# Keyboard.net
KiCad netlist of a schematic drawn in Altium Designer
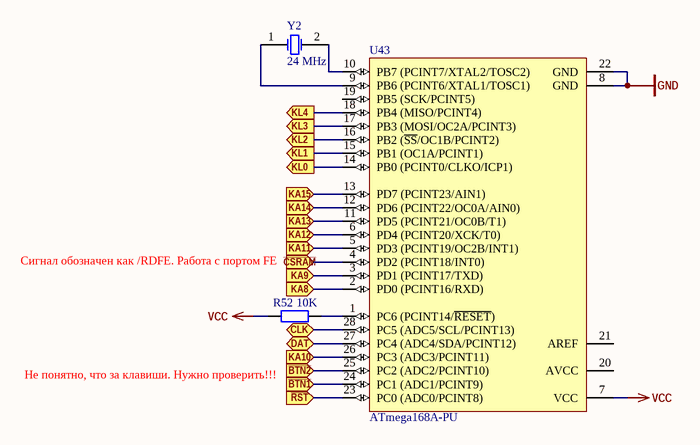
[diagram p0: Keyboard.SchDoc]

(export (version "E")
  (design (tool "Eeschema 10.0.6"))
  (components
    (comp (ref "R52")
      (value "10K")
      (footprint "Lenin:AXIAL-0.4")
      (description "Resistor")
      (fields (field (name "Comment") "Res2") (field (name "PUBLISHER") "Altium Limited"))
      (libsource (lib "Lenin") (part "Res2"))
    )
    (comp (ref "U43")
      (value "ATmega168A-PU")
      (footprint "28P3")
      (fields (field (name "PUBLISHER") "Altium Limited"))
      (libsource (lib "Atmel Microcontroller 8-Bit megaAVR") (part "ATmega168A-PU"))
    )
    (comp (ref "Y2")
      (value "24 MHz")
      (footprint "Lenin:HC25U")
      (description "Crystal Oscillator")
      (fields (field (name "PUBLISHER") "Altium Limited"))
      (libsource (lib "Lenin") (part "XTAL"))
    )
  )
  (nets
    (net (code "1") (name "/CLK") (class "Default")
      (node (ref "U43") (pin "28") (pinfunction "PC5_(ADC5/SCL/PCINT13)_28") (pintype "bidirectional"))
    )
    (net (code "2") (name "/DAT") (class "Default")
      (node (ref "U43") (pin "27") (pinfunction "PC4_(ADC4/SDA/PCINT12)_27") (pintype "bidirectional"))
    )
    (net (code "3") (name "/KA8") (class "Default")
      (node (ref "U43") (pin "2") (pinfunction "PD0_(PCINT16/RXD)_2") (pintype "bidirectional"))
    )
    (net (code "4") (name "/KA9") (class "Default")
      (node (ref "U43") (pin "3") (pinfunction "PD1_(PCINT17/TXD)_3") (pintype "bidirectional"))
    )
    (net (code "5") (name "/KA10") (class "Default")
      (node (ref "U43") (pin "26") (pinfunction "PC3_(ADC3/PCINT11)_26") (pintype "bidirectional"))
    )
    (net (code "6") (name "/KA11") (class "Default")
      (node (ref "U43") (pin "5") (pinfunction "PD3_(PCINT19/OC2B/INT1)_5") (pintype "bidirectional"))
    )
    (net (code "7") (name "/KA12") (class "Default")
      (node (ref "U43") (pin "6") (pinfunction "PD4_(PCINT20/XCK/T0)_6") (pintype "bidirectional"))
    )
    (net (code "8") (name "/KA13") (class "Default")
      (node (ref "U43") (pin "11") (pinfunction "PD5_(PCINT21/OC0B/T1)_11") (pintype "bidirectional"))
    )
    (net (code "9") (name "/KA14") (class "Default")
      (node (ref "U43") (pin "12") (pinfunction "PD6_(PCINT22/OC0A/AIN0)_12") (pintype "bidirectional"))
    )
    (net (code "10") (name "/KA15") (class "Default")
      (node (ref "U43") (pin "13") (pinfunction "PD7_(PCINT23/AIN1)_13") (pintype "bidirectional"))
    )
    (net (code "11") (name "/KL0") (class "Default")
      (node (ref "U43") (pin "14") (pinfunction "PB0_(PCINT0/CLKO/ICP1)_14") (pintype "bidirectional"))
    )
    (net (code "12") (name "/KL1") (class "Default")
      (node (ref "U43") (pin "15") (pinfunction "PB1_(OC1A/PCINT1)_15") (pintype "bidirectional"))
    )
    (net (code "13") (name "/KL2") (class "Default")
      (node (ref "U43") (pin "16") (pinfunction "PB2_(~{SS}/OC1B/PCINT2)_16") (pintype "bidirectional"))
    )
    (net (code "14") (name "/KL3") (class "Default")
      (node (ref "U43") (pin "17") (pinfunction "PB3_(MOSI/OC2A/PCINT3)_17") (pintype "bidirectional"))
    )
    (net (code "15") (name "/KL4") (class "Default")
      (node (ref "U43") (pin "18") (pinfunction "PB4_(MISO/PCINT4)_18") (pintype "bidirectional"))
    )
    (net (code "16") (name "/~{BTN1}") (class "Default")
      (node (ref "U43") (pin "24") (pinfunction "PC1_(ADC1/PCINT9)_24") (pintype "bidirectional"))
    )
    (net (code "17") (name "/~{BTN2}") (class "Default")
      (node (ref "U43") (pin "25") (pinfunction "PC2_(ADC2/PCINT10)_25") (pintype "bidirectional"))
    )
    (net (code "18") (name "/~{CSRAM}") (class "Default")
      (node (ref "U43") (pin "4") (pinfunction "PD2_(PCINT18/INT0)_4") (pintype "bidirectional"))
    )
    (net (code "19") (name "/~{RST}") (class "Default")
      (node (ref "U43") (pin "23") (pinfunction "PC0_(ADC0/PCINT8)_23") (pintype "bidirectional"))
    )
    (net (code "20") (name "GND") (class "Default")
      (node (ref "U43") (pin "22") (pinfunction "GND_22") (pintype "power_in"))
      (node (ref "U43") (pin "8") (pinfunction "GND_8") (pintype "power_in"))
    )
    (net (code "21") (name "Net-(U43-PB6_(PCINT6{slash}XTAL1{slash}TOSC1))") (class "Default")
      (node (ref "U43") (pin "9") (pinfunction "PB6_(PCINT6/XTAL1/TOSC1)_9") (pintype "bidirectional"))
      (node (ref "Y2") (pin "1") (pinfunction "OSC1_1") (pintype "passive"))
    )
    (net (code "22") (name "Net-(U43-PB7_(PCINT7{slash}XTAL2{slash}TOSC2))") (class "Default")
      (node (ref "U43") (pin "10") (pinfunction "PB7_(PCINT7/XTAL2/TOSC2)_10") (pintype "bidirectional"))
      (node (ref "Y2") (pin "2") (pinfunction "OSC2_2") (pintype "passive"))
    )
    (net (code "23") (name "Net-(U43-PC6_(PCINT14{slash}~{RESET}))") (class "Default")
      (node (ref "R52") (pin "1") (pinfunction "1_1") (pintype "passive"))
      (node (ref "U43") (pin "1") (pinfunction "PC6_(PCINT14/~{RESET})_1") (pintype "bidirectional"))
    )
    (net (code "24") (name "VCC") (class "Default")
      (node (ref "R52") (pin "2") (pinfunction "2_2") (pintype "passive"))
      (node (ref "U43") (pin "7") (pinfunction "VCC_7") (pintype "power_in"))
    )
    (net (code "25") (name "unconnected-(U43-AREF-Pad21)") (class "Default")
      (node (ref "U43") (pin "21") (pinfunction "AREF_21") (pintype "power_in"))
    )
    (net (code "26") (name "unconnected-(U43-AVCC-Pad20)") (class "Default")
      (node (ref "U43") (pin "20") (pinfunction "AVCC_20") (pintype "power_in"))
    )
    (net (code "27") (name "unconnected-(U43-PB5_(SCK{slash}PCINT5)-Pad19)") (class "Default")
      (node (ref "U43") (pin "19") (pinfunction "PB5_(SCK/PCINT5)_19") (pintype "bidirectional"))
    )
  )
)
